# base_v4.net
KiCad netlist of a schematic drawn in EAGLE
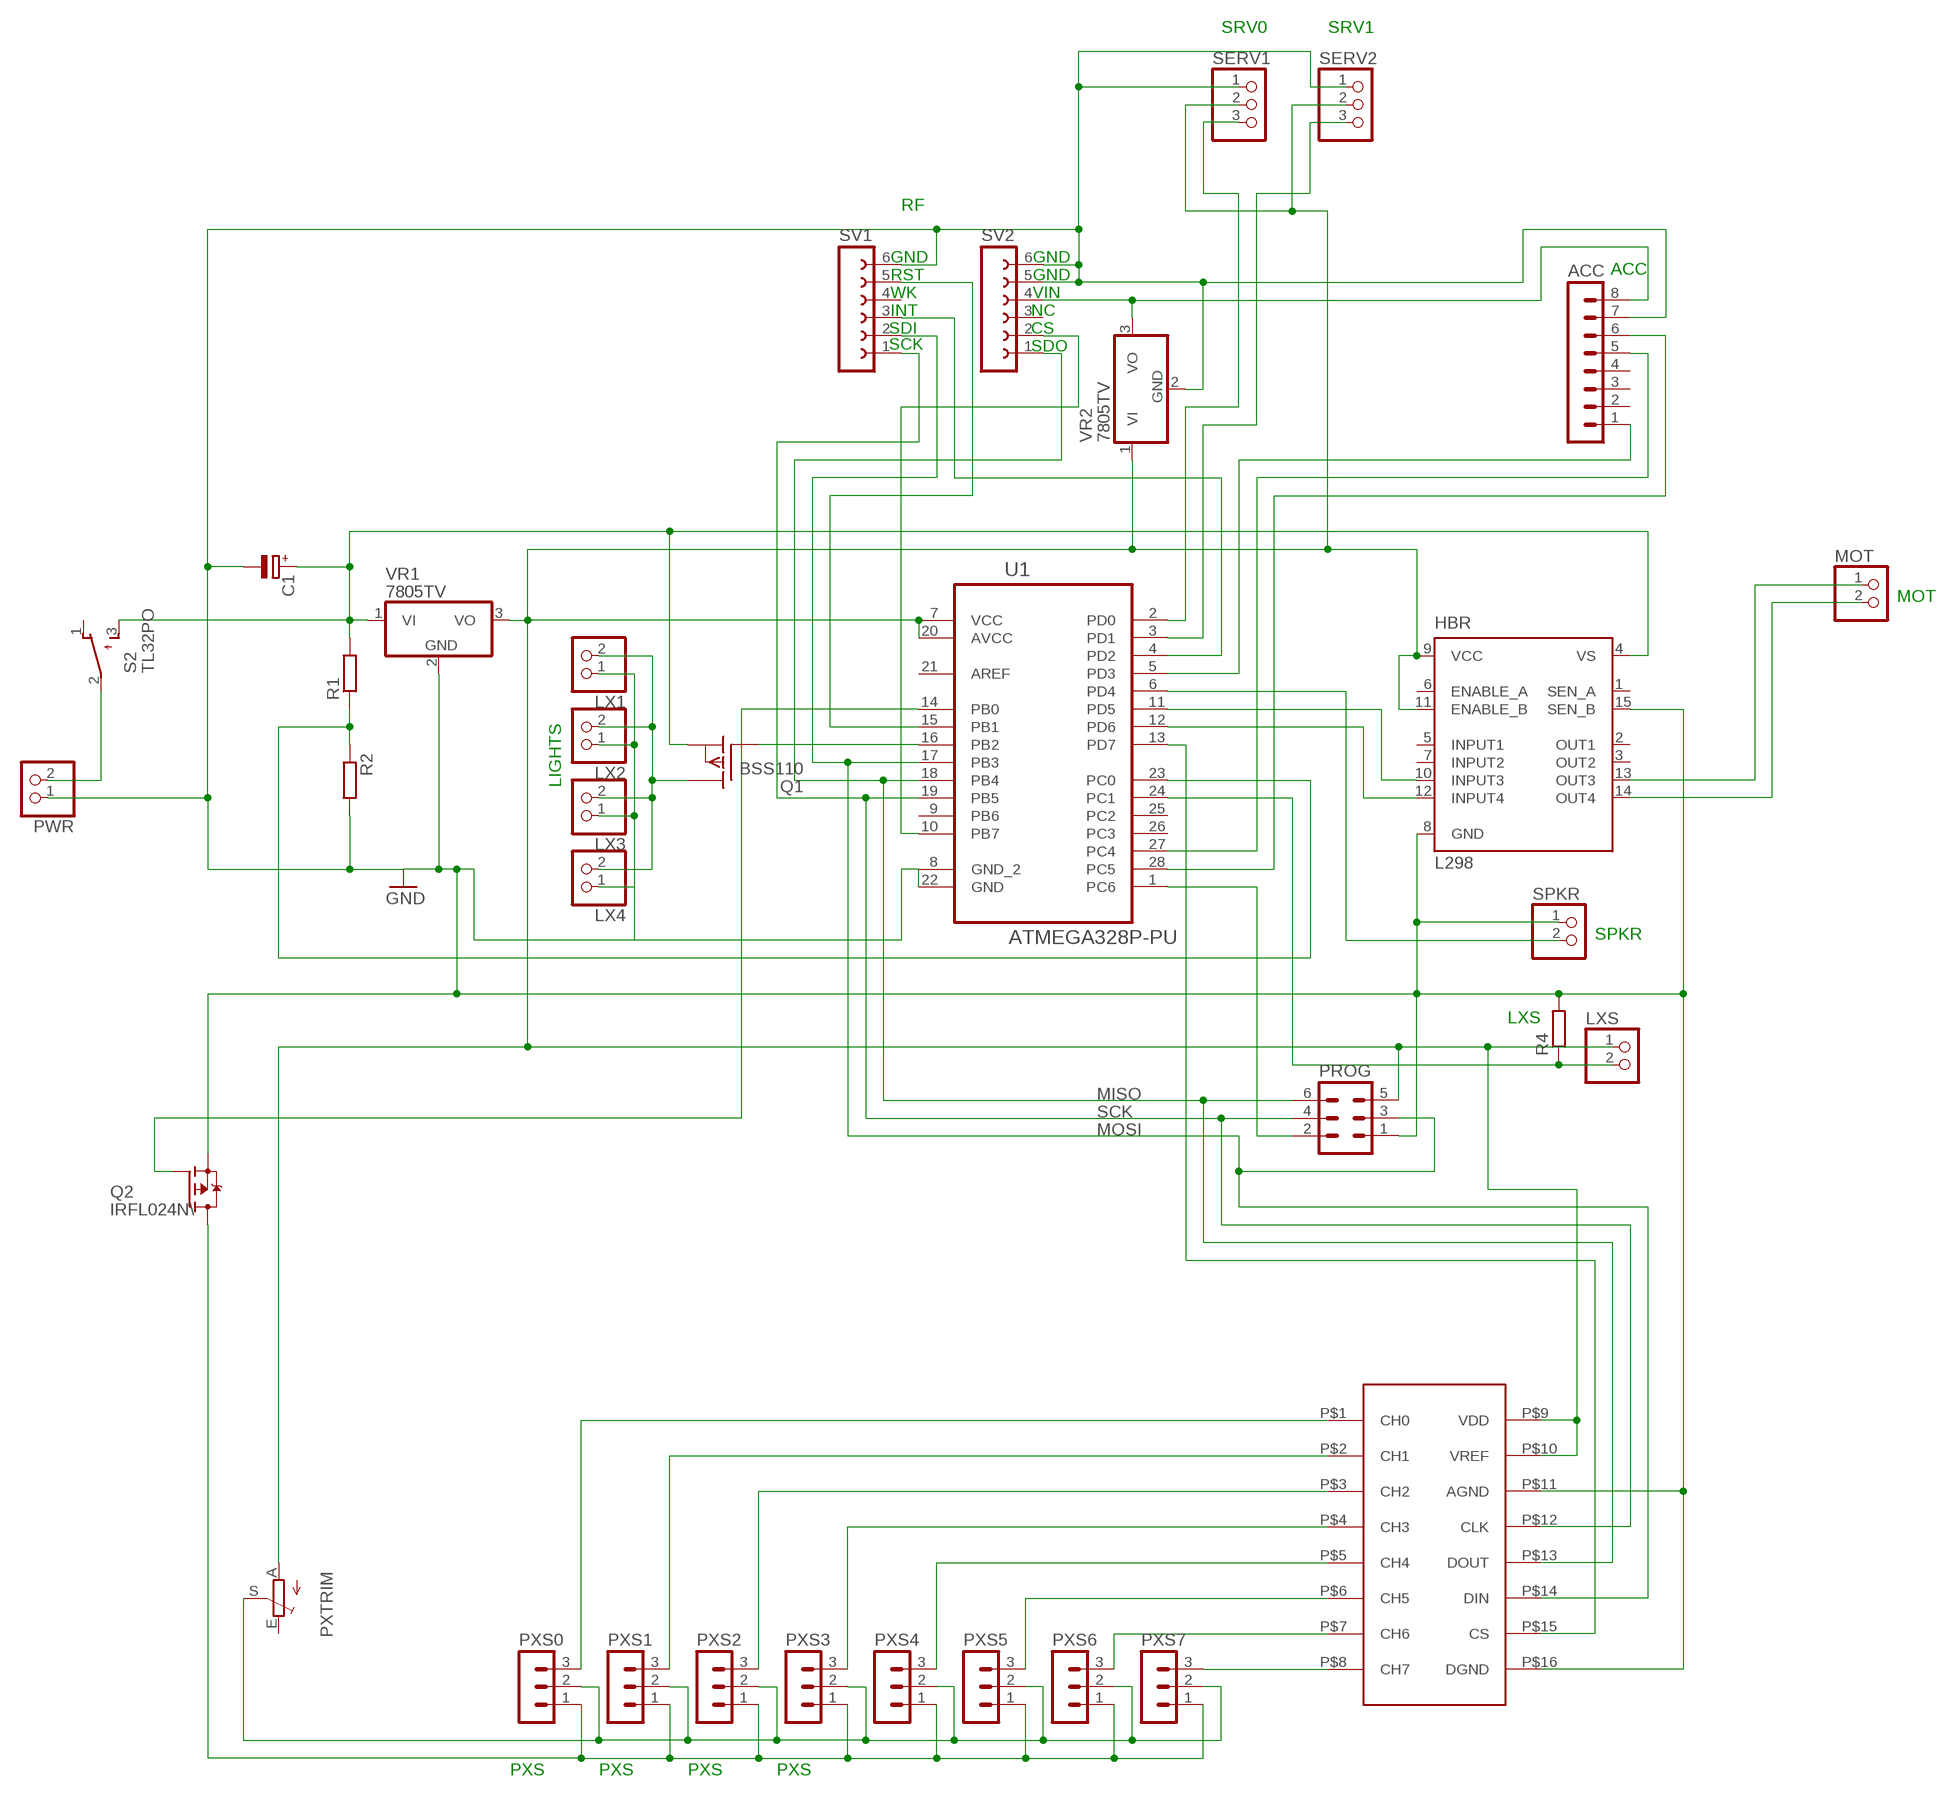
[diagram p0: schematic, sheet 1]

(export (version "E")
  (design (tool "Eeschema 10.0.6"))
  (components
    (comp (ref "ACC")
      (value "MA08-1")
      (footprint "eagle-import:MA08-1")
      (libsource (lib "eagle-import") (part "MA08-1"))
    )
    (comp (ref "C1")
      (value "CPOL-EUE2.5-7")
      (footprint "eagle-import:E2,5-7")
      (libsource (lib "eagle-import") (part "CPOL-EUE2.5-7"))
    )
    (comp (ref "HBR")
      (value "L298")
      (footprint "eagle-import:MULTIWATT-15")
      (fields (field (name "MPN") "L298N"))
      (libsource (lib "eagle-import") (part "L298"))
    )
    (comp (ref "LX1")
      (value "PINHD-1X2")
      (footprint "eagle-import:1X02")
      (libsource (lib "eagle-import") (part "PINHD-1X2"))
    )
    (comp (ref "LX2")
      (value "PINHD-1X2")
      (footprint "eagle-import:1X02")
      (libsource (lib "eagle-import") (part "PINHD-1X2"))
    )
    (comp (ref "LX3")
      (value "PINHD-1X2")
      (footprint "eagle-import:1X02")
      (libsource (lib "eagle-import") (part "PINHD-1X2"))
    )
    (comp (ref "LX4")
      (value "PINHD-1X2")
      (footprint "eagle-import:1X02")
      (libsource (lib "eagle-import") (part "PINHD-1X2"))
    )
    (comp (ref "LXS")
      (value "PINHD-1X2")
      (footprint "eagle-import:1X02")
      (libsource (lib "eagle-import") (part "PINHD-1X2"))
    )
    (comp (ref "MOT")
      (value "PINHD-1X2")
      (footprint "eagle-import:1X02")
      (libsource (lib "eagle-import") (part "PINHD-1X2"))
    )
    (comp (ref "PROG")
      (value "MA03-2")
      (footprint "eagle-import:MA03-2")
      (libsource (lib "eagle-import") (part "MA03-2"))
    )
    (comp (ref "PWR")
      (value "PINHD-1X2")
      (footprint "eagle-import:1X02")
      (libsource (lib "eagle-import") (part "PINHD-1X2"))
    )
    (comp (ref "PXS0")
      (value "MA03-1")
      (footprint "eagle-import:MA03-1")
      (libsource (lib "eagle-import") (part "MA03-1"))
    )
    (comp (ref "PXS1")
      (value "MA03-1")
      (footprint "eagle-import:MA03-1")
      (libsource (lib "eagle-import") (part "MA03-1"))
    )
    (comp (ref "PXS2")
      (value "MA03-1")
      (footprint "eagle-import:MA03-1")
      (libsource (lib "eagle-import") (part "MA03-1"))
    )
    (comp (ref "PXS3")
      (value "MA03-1")
      (footprint "eagle-import:MA03-1")
      (libsource (lib "eagle-import") (part "MA03-1"))
    )
    (comp (ref "PXS4")
      (value "MA03-1")
      (footprint "eagle-import:MA03-1")
      (libsource (lib "eagle-import") (part "MA03-1"))
    )
    (comp (ref "PXS5")
      (value "MA03-1")
      (footprint "eagle-import:MA03-1")
      (libsource (lib "eagle-import") (part "MA03-1"))
    )
    (comp (ref "PXS6")
      (value "MA03-1")
      (footprint "eagle-import:MA03-1")
      (libsource (lib "eagle-import") (part "MA03-1"))
    )
    (comp (ref "PXS7")
      (value "MA03-1")
      (footprint "eagle-import:MA03-1")
      (libsource (lib "eagle-import") (part "MA03-1"))
    )
    (comp (ref "PXTRIM")
      (value "TRIM_EU-CA9V")
      (footprint "eagle-import:CA9V")
      (libsource (lib "eagle-import") (part "TRIM_EU-CA9V"))
    )
    (comp (ref "Q1")
      (value "BSS110")
      (footprint "eagle-import:TO92")
      (libsource (lib "eagle-import") (part "BSS110"))
    )
    (comp (ref "Q2")
      (value "IRFL024N\\")
      (footprint "eagle-import:SOT223")
      (libsource (lib "eagle-import") (part "BSP170P"))
    )
    (comp (ref "R1")
      (value "R-EU_0309/V")
      (footprint "eagle-import:0309V")
      (libsource (lib "eagle-import") (part "R-EU_0309/V"))
    )
    (comp (ref "R2")
      (value "R-EU_0309/V")
      (footprint "eagle-import:0309V")
      (libsource (lib "eagle-import") (part "R-EU_0309/V"))
    )
    (comp (ref "R4")
      (value "R-EU_0309/V")
      (footprint "eagle-import:0309V")
      (libsource (lib "eagle-import") (part "R-EU_0309/V"))
    )
    (comp (ref "S2")
      (value "TL32PO")
      (footprint "eagle-import:TL3XPO")
      (libsource (lib "eagle-import") (part "TL32PO"))
    )
    (comp (ref "SERV1")
      (value "PINHD-1X3")
      (footprint "eagle-import:1X03")
      (libsource (lib "eagle-import") (part "PINHD-1X3"))
    )
    (comp (ref "SERV2")
      (value "PINHD-1X3")
      (footprint "eagle-import:1X03")
      (libsource (lib "eagle-import") (part "PINHD-1X3"))
    )
    (comp (ref "SPKR")
      (value "PINHD-1X2")
      (footprint "eagle-import:1X02")
      (libsource (lib "eagle-import") (part "PINHD-1X2"))
    )
    (comp (ref "SV1")
      (value "FE06-1")
      (footprint "eagle-import:FE06")
      (libsource (lib "eagle-import") (part "FE06-1"))
    )
    (comp (ref "SV2")
      (value "FE06-1")
      (footprint "eagle-import:FE06")
      (libsource (lib "eagle-import") (part "FE06-1"))
    )
    (comp (ref "U$1")
      (value "MCP3208")
      (footprint "eagle-import:DIP16")
      (libsource (lib "eagle-import") (part "MCP3208"))
    )
    (comp (ref "U1")
      (value "ATMEGA328P-PU")
      (footprint "eagle-import:DIP254P762X457-28")
      (libsource (lib "eagle-import") (part "ATMEGA328P-PU"))
    )
    (comp (ref "VR1")
      (value "7805TV")
      (footprint "eagle-import:TO220V")
      (libsource (lib "eagle-import") (part "78TV05"))
    )
    (comp (ref "VR2")
      (value "7805TV")
      (footprint "eagle-import:TO220V")
      (libsource (lib "eagle-import") (part "78TV05"))
    )
  )
  (nets
    (net (code "1") (name "/MISO") (class "Default")
      (node (ref "PROG") (pin "6") (pinfunction "6_6") (pintype "passive"))
      (node (ref "SV2") (pin "1") (pinfunction "1_1") (pintype "passive"))
      (node (ref "U$1") (pin "P$13") (pinfunction "DOUT_P$13") (pintype "bidirectional"))
      (node (ref "U1") (pin "18") (pinfunction "PB4_18") (pintype "bidirectional"))
    )
    (net (code "2") (name "/MOSI") (class "Default")
      (node (ref "PROG") (pin "3") (pinfunction "3_3") (pintype "passive"))
      (node (ref "SV1") (pin "2") (pinfunction "2_2") (pintype "passive"))
      (node (ref "U$1") (pin "P$14") (pinfunction "DIN_P$14") (pintype "bidirectional"))
      (node (ref "U1") (pin "17") (pinfunction "PB3_17") (pintype "bidirectional"))
    )
    (net (code "3") (name "/SCK") (class "Default")
      (node (ref "PROG") (pin "4") (pinfunction "4_4") (pintype "passive"))
      (node (ref "SV1") (pin "1") (pinfunction "1_1") (pintype "passive"))
      (node (ref "U$1") (pin "P$12") (pinfunction "CLK_P$12") (pintype "bidirectional"))
      (node (ref "U1") (pin "19") (pinfunction "PB5_19") (pintype "bidirectional"))
    )
    (net (code "4") (name "GND") (class "Default")
      (node (ref "ACC") (pin "7") (pinfunction "7_7") (pintype "passive"))
      (node (ref "C1") (pin "-") (pinfunction "-_-") (pintype "passive"))
      (node (ref "HBR") (pin "15") (pinfunction "SEN_B_15") (pintype "input"))
      (node (ref "HBR") (pin "8") (pinfunction "GND_8") (pintype "power_in"))
      (node (ref "LX1") (pin "1") (pinfunction "1_1") (pintype "passive"))
      (node (ref "LX2") (pin "1") (pinfunction "1_1") (pintype "passive"))
      (node (ref "LX3") (pin "1") (pinfunction "1_1") (pintype "passive"))
      (node (ref "LX4") (pin "1") (pinfunction "1_1") (pintype "passive"))
      (node (ref "PROG") (pin "1") (pinfunction "1_1") (pintype "passive"))
      (node (ref "PWR") (pin "1") (pinfunction "1_1") (pintype "passive"))
      (node (ref "Q2") (pin "3") (pinfunction "S_3") (pintype "passive"))
      (node (ref "R2") (pin "2") (pinfunction "2_2") (pintype "passive"))
      (node (ref "R4") (pin "2") (pinfunction "2_2") (pintype "passive"))
      (node (ref "SERV1") (pin "1") (pinfunction "1_1") (pintype "passive"))
      (node (ref "SERV2") (pin "1") (pinfunction "1_1") (pintype "passive"))
      (node (ref "SPKR") (pin "1") (pinfunction "1_1") (pintype "passive"))
      (node (ref "SV1") (pin "6") (pinfunction "6_6") (pintype "passive"))
      (node (ref "SV2") (pin "5") (pinfunction "5_5") (pintype "passive"))
      (node (ref "SV2") (pin "6") (pinfunction "6_6") (pintype "passive"))
      (node (ref "U$1") (pin "P$11") (pinfunction "AGND_P$11") (pintype "bidirectional"))
      (node (ref "U$1") (pin "P$16") (pinfunction "DGND_P$16") (pintype "bidirectional"))
      (node (ref "U1") (pin "22") (pinfunction "GND_22") (pintype "passive"))
      (node (ref "U1") (pin "8") (pinfunction "GND_2_8") (pintype "passive"))
      (node (ref "VR1") (pin "2") (pinfunction "GND_2") (pintype "passive"))
      (node (ref "VR2") (pin "2") (pinfunction "GND_2") (pintype "passive"))
    )
    (net (code "5") (name "Net-(HBR-ENABLE_B)") (class "Default")
      (node (ref "HBR") (pin "11") (pinfunction "ENABLE_B_11") (pintype "input"))
      (node (ref "HBR") (pin "9") (pinfunction "VCC_9") (pintype "power_in"))
      (node (ref "LXS") (pin "1") (pinfunction "1_1") (pintype "passive"))
      (node (ref "PROG") (pin "5") (pinfunction "5_5") (pintype "passive"))
      (node (ref "PXTRIM") (pin "A") (pinfunction "A_A") (pintype "passive"))
      (node (ref "SERV1") (pin "2") (pinfunction "2_2") (pintype "passive"))
      (node (ref "SERV2") (pin "2") (pinfunction "2_2") (pintype "passive"))
      (node (ref "U$1") (pin "P$10") (pinfunction "VREF_P$10") (pintype "bidirectional"))
      (node (ref "U$1") (pin "P$9") (pinfunction "VDD_P$9") (pintype "bidirectional"))
      (node (ref "U1") (pin "20") (pinfunction "AVCC_20") (pintype "power_in"))
      (node (ref "U1") (pin "7") (pinfunction "VCC_7") (pintype "power_in"))
      (node (ref "VR1") (pin "3") (pinfunction "VO_3") (pintype "passive"))
      (node (ref "VR2") (pin "1") (pinfunction "VI_1") (pintype "input"))
    )
    (net (code "6") (name "Net-(HBR-INPUT3)") (class "Default")
      (node (ref "HBR") (pin "10") (pinfunction "INPUT3_10") (pintype "input"))
      (node (ref "U1") (pin "11") (pinfunction "PD5_11") (pintype "bidirectional"))
    )
    (net (code "7") (name "Net-(HBR-INPUT4)") (class "Default")
      (node (ref "HBR") (pin "12") (pinfunction "INPUT4_12") (pintype "input"))
      (node (ref "U1") (pin "12") (pinfunction "PD6_12") (pintype "bidirectional"))
    )
    (net (code "8") (name "Net-(HBR-OUT3)") (class "Default")
      (node (ref "HBR") (pin "13") (pinfunction "OUT3_13") (pintype "output"))
      (node (ref "MOT") (pin "1") (pinfunction "1_1") (pintype "passive"))
    )
    (net (code "9") (name "Net-(HBR-OUT4)") (class "Default")
      (node (ref "HBR") (pin "14") (pinfunction "OUT4_14") (pintype "output"))
      (node (ref "MOT") (pin "2") (pinfunction "2_2") (pintype "passive"))
    )
    (net (code "10") (name "Net-(HBR-VS)") (class "Default")
      (node (ref "C1") (pin "+") (pinfunction "+_+") (pintype "passive"))
      (node (ref "HBR") (pin "4") (pinfunction "VS_4") (pintype "power_in"))
      (node (ref "Q1") (pin "1") (pinfunction "S_1") (pintype "passive"))
      (node (ref "R1") (pin "2") (pinfunction "2_2") (pintype "passive"))
      (node (ref "S2") (pin "3") (pinfunction "S_3") (pintype "passive"))
      (node (ref "VR1") (pin "1") (pinfunction "VI_1") (pintype "input"))
    )
    (net (code "11") (name "Net-(PXS0-Pad1)") (class "Default")
      (node (ref "PXS0") (pin "1") (pinfunction "1_1") (pintype "passive"))
      (node (ref "PXS1") (pin "1") (pinfunction "1_1") (pintype "passive"))
      (node (ref "PXS2") (pin "1") (pinfunction "1_1") (pintype "passive"))
      (node (ref "PXS3") (pin "1") (pinfunction "1_1") (pintype "passive"))
      (node (ref "PXS4") (pin "1") (pinfunction "1_1") (pintype "passive"))
      (node (ref "PXS5") (pin "1") (pinfunction "1_1") (pintype "passive"))
      (node (ref "PXS6") (pin "1") (pinfunction "1_1") (pintype "passive"))
      (node (ref "PXS7") (pin "1") (pinfunction "1_1") (pintype "passive"))
      (node (ref "Q2") (pin "2") (pinfunction "D_2") (pintype "passive"))
      (node (ref "Q2") (pin "4") (pinfunction "D_4") (pintype "passive"))
    )
    (net (code "12") (name "Net-(PXS0-Pad2)") (class "Default")
      (node (ref "PXS0") (pin "2") (pinfunction "2_2") (pintype "passive"))
      (node (ref "PXS1") (pin "2") (pinfunction "2_2") (pintype "passive"))
      (node (ref "PXS2") (pin "2") (pinfunction "2_2") (pintype "passive"))
      (node (ref "PXS3") (pin "2") (pinfunction "2_2") (pintype "passive"))
      (node (ref "PXS4") (pin "2") (pinfunction "2_2") (pintype "passive"))
      (node (ref "PXS5") (pin "2") (pinfunction "2_2") (pintype "passive"))
      (node (ref "PXS6") (pin "2") (pinfunction "2_2") (pintype "passive"))
      (node (ref "PXS7") (pin "2") (pinfunction "2_2") (pintype "passive"))
      (node (ref "PXTRIM") (pin "S") (pinfunction "S_S") (pintype "passive"))
    )
    (net (code "13") (name "Net-(Q1-D)") (class "Default")
      (node (ref "LX1") (pin "2") (pinfunction "2_2") (pintype "passive"))
      (node (ref "LX2") (pin "2") (pinfunction "2_2") (pintype "passive"))
      (node (ref "LX3") (pin "2") (pinfunction "2_2") (pintype "passive"))
      (node (ref "LX4") (pin "2") (pinfunction "2_2") (pintype "passive"))
      (node (ref "Q1") (pin "3") (pinfunction "D_3") (pintype "passive"))
    )
    (net (code "14") (name "Net-(Q1-G)") (class "Default")
      (node (ref "Q1") (pin "2") (pinfunction "G_2") (pintype "passive"))
      (node (ref "U1") (pin "16") (pinfunction "PB2_16") (pintype "bidirectional"))
    )
    (net (code "15") (name "Net-(Q2-G)") (class "Default")
      (node (ref "Q2") (pin "1") (pinfunction "G_1") (pintype "passive"))
      (node (ref "U1") (pin "14") (pinfunction "PB0_14") (pintype "bidirectional"))
    )
    (net (code "16") (name "Net-(S2-P)") (class "Default")
      (node (ref "PWR") (pin "2") (pinfunction "2_2") (pintype "passive"))
      (node (ref "S2") (pin "2") (pinfunction "P_2") (pintype "passive"))
    )
    (net (code "17") (name "Net-(U$1-CH0)") (class "Default")
      (node (ref "PXS0") (pin "3") (pinfunction "3_3") (pintype "passive"))
      (node (ref "U$1") (pin "P$1") (pinfunction "CH0_P$1") (pintype "bidirectional"))
    )
    (net (code "18") (name "Net-(U$1-CH1)") (class "Default")
      (node (ref "PXS1") (pin "3") (pinfunction "3_3") (pintype "passive"))
      (node (ref "U$1") (pin "P$2") (pinfunction "CH1_P$2") (pintype "bidirectional"))
    )
    (net (code "19") (name "Net-(U$1-CH2)") (class "Default")
      (node (ref "PXS2") (pin "3") (pinfunction "3_3") (pintype "passive"))
      (node (ref "U$1") (pin "P$3") (pinfunction "CH2_P$3") (pintype "bidirectional"))
    )
    (net (code "20") (name "Net-(U$1-CH3)") (class "Default")
      (node (ref "PXS3") (pin "3") (pinfunction "3_3") (pintype "passive"))
      (node (ref "U$1") (pin "P$4") (pinfunction "CH3_P$4") (pintype "bidirectional"))
    )
    (net (code "21") (name "Net-(U$1-CH4)") (class "Default")
      (node (ref "PXS4") (pin "3") (pinfunction "3_3") (pintype "passive"))
      (node (ref "U$1") (pin "P$5") (pinfunction "CH4_P$5") (pintype "bidirectional"))
    )
    (net (code "22") (name "Net-(U$1-CH5)") (class "Default")
      (node (ref "PXS5") (pin "3") (pinfunction "3_3") (pintype "passive"))
      (node (ref "U$1") (pin "P$6") (pinfunction "CH5_P$6") (pintype "bidirectional"))
    )
    (net (code "23") (name "Net-(U$1-CH6)") (class "Default")
      (node (ref "PXS6") (pin "3") (pinfunction "3_3") (pintype "passive"))
      (node (ref "U$1") (pin "P$7") (pinfunction "CH6_P$7") (pintype "bidirectional"))
    )
    (net (code "24") (name "Net-(U$1-CH7)") (class "Default")
      (node (ref "PXS7") (pin "3") (pinfunction "3_3") (pintype "passive"))
      (node (ref "U$1") (pin "P$8") (pinfunction "CH7_P$8") (pintype "bidirectional"))
    )
    (net (code "25") (name "Net-(U$1-CS)") (class "Default")
      (node (ref "U$1") (pin "P$15") (pinfunction "CS_P$15") (pintype "bidirectional"))
      (node (ref "U1") (pin "13") (pinfunction "PD7_13") (pintype "bidirectional"))
    )
    (net (code "26") (name "Net-(U1-PB1)") (class "Default")
      (node (ref "SV1") (pin "5") (pinfunction "5_5") (pintype "passive"))
      (node (ref "U1") (pin "15") (pinfunction "PB1_15") (pintype "bidirectional"))
    )
    (net (code "27") (name "Net-(U1-PB7)") (class "Default")
      (node (ref "SV2") (pin "2") (pinfunction "2_2") (pintype "passive"))
      (node (ref "U1") (pin "10") (pinfunction "PB7_10") (pintype "bidirectional"))
    )
    (net (code "28") (name "Net-(U1-PC0)") (class "Default")
      (node (ref "R1") (pin "1") (pinfunction "1_1") (pintype "passive"))
      (node (ref "R2") (pin "1") (pinfunction "1_1") (pintype "passive"))
      (node (ref "U1") (pin "23") (pinfunction "PC0_23") (pintype "bidirectional"))
    )
    (net (code "29") (name "Net-(U1-PC1)") (class "Default")
      (node (ref "LXS") (pin "2") (pinfunction "2_2") (pintype "passive"))
      (node (ref "R4") (pin "1") (pinfunction "1_1") (pintype "passive"))
      (node (ref "U1") (pin "24") (pinfunction "PC1_24") (pintype "bidirectional"))
    )
    (net (code "30") (name "Net-(U1-PC4)") (class "Default")
      (node (ref "ACC") (pin "5") (pinfunction "5_5") (pintype "passive"))
      (node (ref "U1") (pin "27") (pinfunction "PC4_27") (pintype "bidirectional"))
    )
    (net (code "31") (name "Net-(U1-PC5)") (class "Default")
      (node (ref "ACC") (pin "6") (pinfunction "6_6") (pintype "passive"))
      (node (ref "U1") (pin "28") (pinfunction "PC5_28") (pintype "bidirectional"))
    )
    (net (code "32") (name "Net-(U1-PC6)") (class "Default")
      (node (ref "PROG") (pin "2") (pinfunction "2_2") (pintype "passive"))
      (node (ref "U1") (pin "1") (pinfunction "PC6_1") (pintype "bidirectional"))
    )
    (net (code "33") (name "Net-(U1-PD0)") (class "Default")
      (node (ref "SERV1") (pin "3") (pinfunction "3_3") (pintype "passive"))
      (node (ref "U1") (pin "2") (pinfunction "PD0_2") (pintype "bidirectional"))
    )
    (net (code "34") (name "Net-(U1-PD1)") (class "Default")
      (node (ref "SERV2") (pin "3") (pinfunction "3_3") (pintype "passive"))
      (node (ref "U1") (pin "3") (pinfunction "PD1_3") (pintype "bidirectional"))
    )
    (net (code "35") (name "Net-(U1-PD2)") (class "Default")
      (node (ref "SV1") (pin "3") (pinfunction "3_3") (pintype "passive"))
      (node (ref "U1") (pin "4") (pinfunction "PD2_4") (pintype "bidirectional"))
    )
    (net (code "36") (name "Net-(U1-PD3)") (class "Default")
      (node (ref "ACC") (pin "1") (pinfunction "1_1") (pintype "passive"))
      (node (ref "U1") (pin "5") (pinfunction "PD3_5") (pintype "bidirectional"))
    )
    (net (code "37") (name "Net-(U1-PD4)") (class "Default")
      (node (ref "SPKR") (pin "2") (pinfunction "2_2") (pintype "passive"))
      (node (ref "U1") (pin "6") (pinfunction "PD4_6") (pintype "bidirectional"))
    )
    (net (code "38") (name "Net-(VR2-VO)") (class "Default")
      (node (ref "ACC") (pin "8") (pinfunction "8_8") (pintype "passive"))
      (node (ref "SV2") (pin "4") (pinfunction "4_4") (pintype "passive"))
      (node (ref "VR2") (pin "3") (pinfunction "VO_3") (pintype "passive"))
    )
    (net (code "39") (name "unconnected-(ACC-Pad2)") (class "Default")
      (node (ref "ACC") (pin "2") (pinfunction "2_2") (pintype "passive"))
    )
    (net (code "40") (name "unconnected-(ACC-Pad3)") (class "Default")
      (node (ref "ACC") (pin "3") (pinfunction "3_3") (pintype "passive"))
    )
    (net (code "41") (name "unconnected-(ACC-Pad4)") (class "Default")
      (node (ref "ACC") (pin "4") (pinfunction "4_4") (pintype "passive"))
    )
    (net (code "42") (name "unconnected-(HBR-ENABLE_A-Pad6)") (class "Default")
      (node (ref "HBR") (pin "6") (pinfunction "ENABLE_A_6") (pintype "input"))
    )
    (net (code "43") (name "unconnected-(HBR-INPUT1-Pad5)") (class "Default")
      (node (ref "HBR") (pin "5") (pinfunction "INPUT1_5") (pintype "input"))
    )
    (net (code "44") (name "unconnected-(HBR-INPUT2-Pad7)") (class "Default")
      (node (ref "HBR") (pin "7") (pinfunction "INPUT2_7") (pintype "input"))
    )
    (net (code "45") (name "unconnected-(HBR-OUT1-Pad2)") (class "Default")
      (node (ref "HBR") (pin "2") (pinfunction "OUT1_2") (pintype "output"))
    )
    (net (code "46") (name "unconnected-(HBR-OUT2-Pad3)") (class "Default")
      (node (ref "HBR") (pin "3") (pinfunction "OUT2_3") (pintype "output"))
    )
    (net (code "47") (name "unconnected-(HBR-SEN_A-Pad1)") (class "Default")
      (node (ref "HBR") (pin "1") (pinfunction "SEN_A_1") (pintype "input"))
    )
    (net (code "48") (name "unconnected-(PXTRIM-PadE)") (class "Default")
      (node (ref "PXTRIM") (pin "E") (pinfunction "E_E") (pintype "passive"))
    )
    (net (code "49") (name "unconnected-(S2-O-Pad1)") (class "Default")
      (node (ref "S2") (pin "1") (pinfunction "O_1") (pintype "passive"))
    )
    (net (code "50") (name "unconnected-(SV1-Pad4)") (class "Default")
      (node (ref "SV1") (pin "4") (pinfunction "4_4") (pintype "passive"))
    )
    (net (code "51") (name "unconnected-(SV2-Pad3)") (class "Default")
      (node (ref "SV2") (pin "3") (pinfunction "3_3") (pintype "passive"))
    )
    (net (code "52") (name "unconnected-(U1-AREF-Pad21)") (class "Default")
      (node (ref "U1") (pin "21") (pinfunction "AREF_21") (pintype "input"))
    )
    (net (code "53") (name "unconnected-(U1-PB6-Pad9)") (class "Default")
      (node (ref "U1") (pin "9") (pinfunction "PB6_9") (pintype "bidirectional"))
    )
    (net (code "54") (name "unconnected-(U1-PC2-Pad25)") (class "Default")
      (node (ref "U1") (pin "25") (pinfunction "PC2_25") (pintype "bidirectional"))
    )
    (net (code "55") (name "unconnected-(U1-PC3-Pad26)") (class "Default")
      (node (ref "U1") (pin "26") (pinfunction "PC3_26") (pintype "bidirectional"))
    )
  )
)
